# Sheet1.net
KiCad netlist of a schematic drawn in Altium Designer
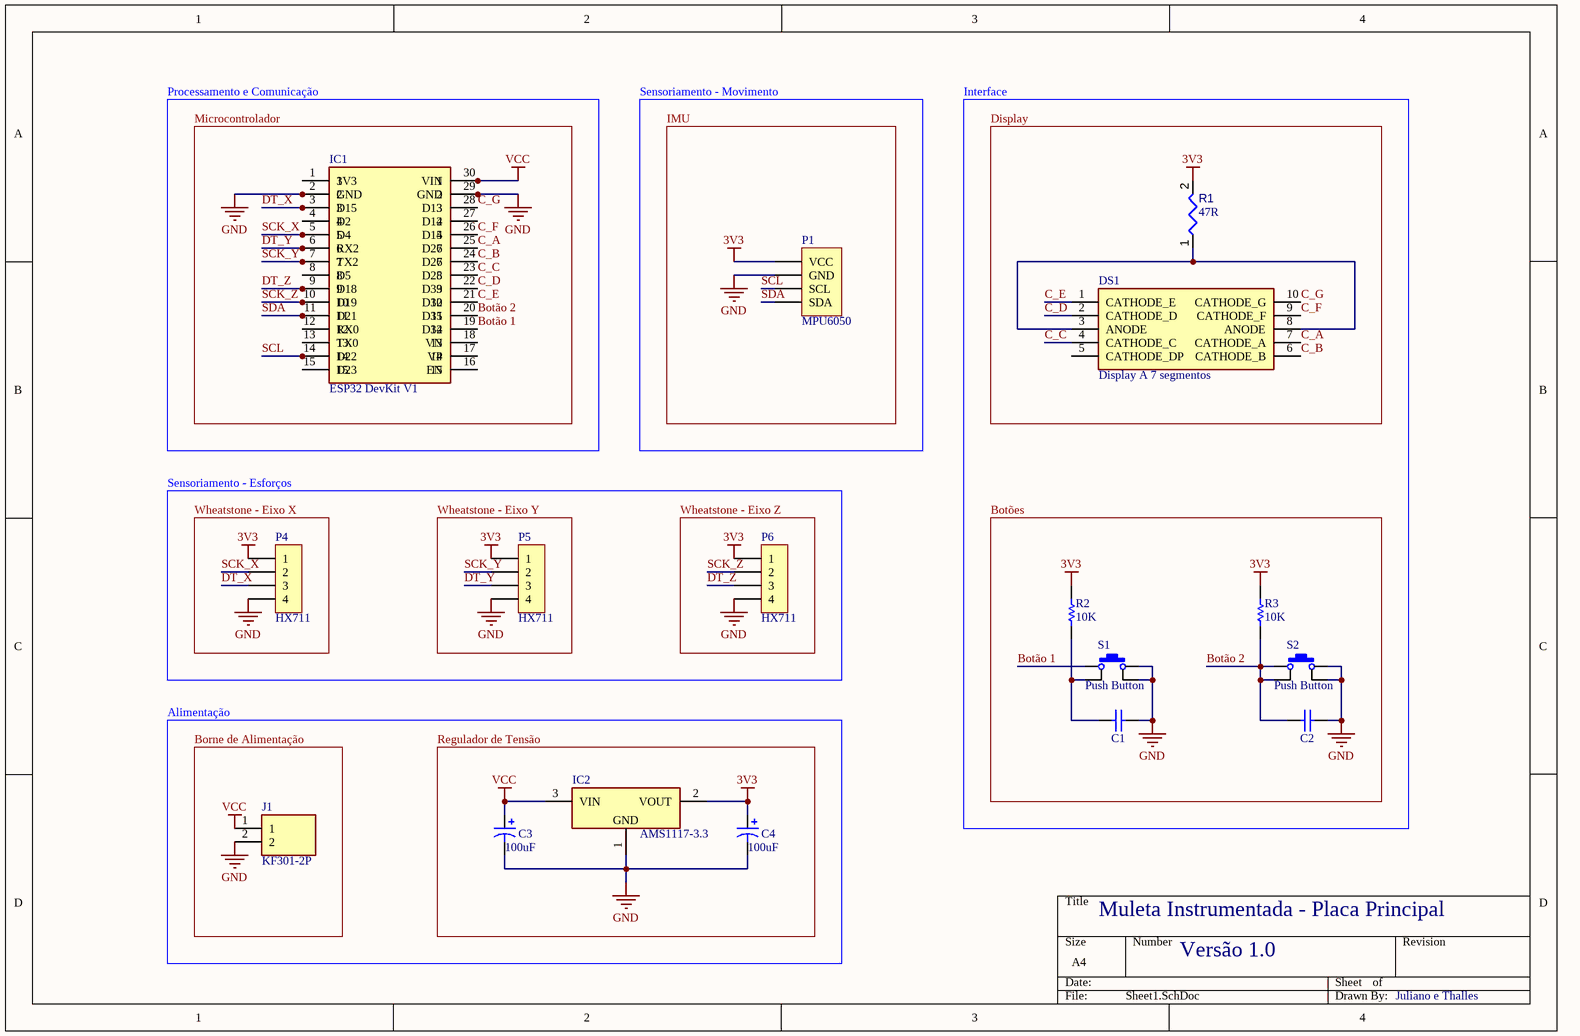
[diagram p0: Sheet1.SchDoc]

(export (version "E")
  (design (tool "Eeschema 10.0.6"))
  (components
    (comp (ref "C1")
      (value "CAP CER DISK 100NF 50V")
      (footprint "CAP CER DISK 100NF 50V")
      (fields (field (name "MANUFACTURER PART NUMBER") "IMP14925"))
      (libsource (lib "ThundeRatz") (part "Symbol"))
    )
    (comp (ref "C2")
      (value "CAP CER DISK 100NF 50V")
      (footprint "CAP CER DISK 100NF 50V")
      (fields (field (name "MANUFACTURER PART NUMBER") "IMP14925"))
      (libsource (lib "ThundeRatz") (part "Symbol"))
    )
    (comp (ref "C3")
      (value "100uF")
      (footprint "CAPPRD250W65D630H900")
      (description "Capacitor Polarised")
      (fields
        (field (name "MANUFACTURER_PART_NUMBER") "16SEPC100MW+S")
        (field (name "MOUSER PART NUMBER") "667-16SEPC100MW+S")
      )
      (libsource (lib "Schlib1") (part "16SEPC100MW+S"))
    )
    (comp (ref "C4")
      (value "100uF")
      (footprint "CAPPRD250W65D630H900")
      (description "Capacitor Polarised")
      (fields
        (field (name "MANUFACTURER_PART_NUMBER") "16SEPC100MW+S")
        (field (name "MOUSER PART NUMBER") "667-16SEPC100MW+S")
      )
      (libsource (lib "Schlib1") (part "16SEPC100MW+S"))
    )
    (comp (ref "DS1")
      (value "Display A 7 segmentos")
      (footprint "PcbLib1:DIPS1524W51P254L1270H825Q10N")
      (description "Display")
      (fields (field (name "MANUFACTURER_PART_NUMBER") "C-551SRD-NW B/W"))
      (libsource (lib "Schlib1") (part "C-551SRD-NW_B_W"))
    )
    (comp (ref "IC1")
      (value "ESP32 DevKit V1")
      (footprint "PcbLib1:ESP32 DevKit V1")
      (libsource (lib "Schlib1") (part "ESP32 DevKit V1"))
    )
    (comp (ref "IC2")
      (value "AMS1117-3.3")
      (footprint "PcbLib1:SOT229P700X180-4N")
      (description "Integrated Circuit")
      (libsource (lib "Schlib1") (part "AMS1117-3.3"))
    )
    (comp (ref "J1")
      (value "KF301-2P")
      (footprint "KF3012P")
      (description "Connector")
      (libsource (lib "Schlib1") (part "KF301-2P"))
    )
    (comp (ref "P1")
      (value "MPU6050")
      (footprint "Pin Header 1x8 TH Pitch 2.54mm")
      (description "Headers & Wire Housings 36Pin 2mm Spacing Single Row Hdrs, 5pc")
      (libsource (lib "Schlib1") (part "MPU6050 module"))
    )
    (comp (ref "P2")
      (value "Header Female 1x15")
      (footprint "HDR FEMALE 1x15")
      (description "Headers & Wire Housings 40Pin 2mm Spacing Single Row Hdrs, 5pc")
      (fields (field (name "MANUFACTURER") "Cromax"))
      (libsource (lib "Schlib1") (part "Header Female 1x15"))
    )
    (comp (ref "P3")
      (value "Header Female 1x15")
      (footprint "HDR FEMALE 1x15")
      (description "Headers & Wire Housings 40Pin 2mm Spacing Single Row Hdrs, 5pc")
      (fields (field (name "MANUFACTURER") "Cromax"))
      (libsource (lib "") (part "Header Female 1x15_1"))
    )
    (comp (ref "P4")
      (value "HX711")
      (footprint "HDR MALE 1x4")
      (description "Headers & Wire Housings 40Pin 2mm Spacing Single Row Hdrs, 5pc")
      (fields (field (name "MANUFACTURER") "Cromax") (field (name "MANUFACTURER PART NUMBER") "IMP10327"))
      (libsource (lib "Schlib1") (part "Header 1x4"))
    )
    (comp (ref "P5")
      (value "HX711")
      (footprint "HDR MALE 1x4")
      (description "Headers & Wire Housings 40Pin 2mm Spacing Single Row Hdrs, 5pc")
      (fields (field (name "MANUFACTURER") "Cromax") (field (name "MANUFACTURER PART NUMBER") "IMP10327"))
      (libsource (lib "Schlib1") (part "Header 1x4"))
    )
    (comp (ref "P6")
      (value "HX711")
      (footprint "HDR MALE 1x4")
      (description "Headers & Wire Housings 40Pin 2mm Spacing Single Row Hdrs, 5pc")
      (fields (field (name "MANUFACTURER") "Cromax") (field (name "MANUFACTURER PART NUMBER") "IMP10327"))
      (libsource (lib "Schlib1") (part "Header 1x4"))
    )
    (comp (ref "R1")
      (value "47R")
      (footprint "RESA60-630X240")
      (description "Axial Resistor, 47.5 Ohm, +/- 1%, 0.25 W, -55 to 155 degC, 2-Pin THD, RoHS, Bulk")
      (fields (field (name "TOLERANCE") "1%") (field (name "MANUFACTURER") "Yageo"))
      (libsource (lib "") (part "RES-2_1"))
    )
    (comp (ref "R2")
      (value "10K")
      (footprint "RESA60-630X240")
      (description "Axial Resistor, 10 KOhm, +/- 1%, 0.25 W, -55 to 155 degC, 2-Pin THD, RoHS, Bulk")
      (fields (field (name "TOLERANCE") "1%") (field (name "MANUFACTURER") "Yageo"))
      (libsource (lib "ThundeRatz") (part "RES-2"))
    )
    (comp (ref "R3")
      (value "10K")
      (footprint "RESA60-630X240")
      (description "Axial Resistor, 10 KOhm, +/- 1%, 0.25 W, -55 to 155 degC, 2-Pin THD, RoHS, Bulk")
      (fields (field (name "TOLERANCE") "1%") (field (name "MANUFACTURER") "Yageo"))
      (libsource (lib "ThundeRatz") (part "RES-2"))
    )
    (comp (ref "S1")
      (value "Push Button")
      (footprint "TACT SWITCH 6X6X7MM")
      (description "SWITCH TACTILE SPST-NO 0.02A 15V")
      (fields
        (field (name "MANUFACTURER") "Panasonic Electronic Components")
        (field (name "MANUFACTURER PART NUMBER") "EVQ-PAC07K")
      )
      (libsource (lib "ThundeRatz") (part "SWITCH TACTILE SPST-NO 0.02A 15V"))
    )
    (comp (ref "S2")
      (value "Push Button")
      (footprint "TACT SWITCH 6X6X7MM")
      (description "SWITCH TACTILE SPST-NO 0.02A 15V")
      (fields
        (field (name "MANUFACTURER") "Panasonic Electronic Components")
        (field (name "MANUFACTURER PART NUMBER") "EVQ-PAC07K")
      )
      (libsource (lib "ThundeRatz") (part "SWITCH TACTILE SPST-NO 0.02A 15V"))
    )
  )
  (nets
    (net (code "1") (name "/Botão 1") (class "Default")
      (node (ref "IC1") (pin "19") (pinfunction "D34_19") (pintype "passive"))
      (node (ref "P3") (pin "12") (pinfunction "12_12") (pintype "power_in"))
      (node (ref "S1") (pin "1") (pinfunction "1_1") (pintype "passive"))
    )
    (net (code "2") (name "/Botão 2") (class "Default")
      (node (ref "C2") (pin "1") (pinfunction "1_1") (pintype "passive"))
      (node (ref "IC1") (pin "20") (pinfunction "D35_20") (pintype "passive"))
      (node (ref "P3") (pin "11") (pinfunction "11_11") (pintype "power_in"))
      (node (ref "R3") (pin "1") (pinfunction "1_1") (pintype "passive"))
      (node (ref "S2") (pin "1") (pinfunction "1_1") (pintype "passive"))
      (node (ref "S2") (pin "2") (pinfunction "2_2") (pintype "passive"))
    )
    (net (code "3") (name "/C_A") (class "Default")
      (node (ref "DS1") (pin "7") (pinfunction "CATHODE_A_7") (pintype "passive"))
      (node (ref "IC1") (pin "25") (pinfunction "D27_25") (pintype "passive"))
      (node (ref "P3") (pin "6") (pinfunction "6_6") (pintype "passive"))
    )
    (net (code "4") (name "/C_B") (class "Default")
      (node (ref "DS1") (pin "6") (pinfunction "CATHODE_B_6") (pintype "passive"))
      (node (ref "IC1") (pin "24") (pinfunction "D26_24") (pintype "passive"))
      (node (ref "P3") (pin "7") (pinfunction "7_7") (pintype "power_in"))
    )
    (net (code "5") (name "/C_C") (class "Default")
      (node (ref "DS1") (pin "4") (pinfunction "CATHODE_C_4") (pintype "passive"))
      (node (ref "IC1") (pin "23") (pinfunction "D25_23") (pintype "passive"))
      (node (ref "P3") (pin "8") (pinfunction "8_8") (pintype "power_in"))
    )
    (net (code "6") (name "/C_D") (class "Default")
      (node (ref "DS1") (pin "2") (pinfunction "CATHODE_D_2") (pintype "passive"))
      (node (ref "IC1") (pin "22") (pinfunction "D33_22") (pintype "passive"))
      (node (ref "P3") (pin "9") (pinfunction "9_9") (pintype "passive"))
    )
    (net (code "7") (name "/C_E") (class "Default")
      (node (ref "DS1") (pin "1") (pinfunction "CATHODE_E_1") (pintype "passive"))
      (node (ref "IC1") (pin "21") (pinfunction "D32_21") (pintype "passive"))
      (node (ref "P3") (pin "10") (pinfunction "10_10") (pintype "passive"))
    )
    (net (code "8") (name "/C_F") (class "Default")
      (node (ref "DS1") (pin "9") (pinfunction "CATHODE_F_9") (pintype "passive"))
      (node (ref "IC1") (pin "26") (pinfunction "D14_26") (pintype "passive"))
      (node (ref "P3") (pin "5") (pinfunction "5_5") (pintype "passive"))
    )
    (net (code "9") (name "/C_G") (class "Default")
      (node (ref "DS1") (pin "10") (pinfunction "CATHODE_G_10") (pintype "passive"))
      (node (ref "IC1") (pin "28") (pinfunction "D13_28") (pintype "passive"))
      (node (ref "P3") (pin "3") (pinfunction "3_3") (pintype "power_in"))
    )
    (net (code "10") (name "/DT_X") (class "Default")
      (node (ref "IC1") (pin "3") (pinfunction "D15_3") (pintype "passive"))
      (node (ref "P2") (pin "3") (pinfunction "3_3") (pintype "power_in"))
      (node (ref "P4") (pin "3") (pinfunction "3_3") (pintype "power_in"))
    )
    (net (code "11") (name "/DT_Y") (class "Default")
      (node (ref "IC1") (pin "6") (pinfunction "RX2_6") (pintype "passive"))
      (node (ref "P2") (pin "6") (pinfunction "6_6") (pintype "passive"))
      (node (ref "P5") (pin "3") (pinfunction "3_3") (pintype "power_in"))
    )
    (net (code "12") (name "/DT_Z") (class "Default")
      (node (ref "IC1") (pin "9") (pinfunction "D18_9") (pintype "passive"))
      (node (ref "P2") (pin "9") (pinfunction "9_9") (pintype "passive"))
      (node (ref "P6") (pin "3") (pinfunction "3_3") (pintype "power_in"))
    )
    (net (code "13") (name "/SCK_X") (class "Default")
      (node (ref "IC1") (pin "5") (pinfunction "D4_5") (pintype "passive"))
      (node (ref "P2") (pin "5") (pinfunction "5_5") (pintype "passive"))
      (node (ref "P4") (pin "2") (pinfunction "2_2") (pintype "passive"))
    )
    (net (code "14") (name "/SCK_Y") (class "Default")
      (node (ref "IC1") (pin "7") (pinfunction "TX2_7") (pintype "passive"))
      (node (ref "P2") (pin "7") (pinfunction "7_7") (pintype "power_in"))
      (node (ref "P5") (pin "2") (pinfunction "2_2") (pintype "passive"))
    )
    (net (code "15") (name "/SCK_Z") (class "Default")
      (node (ref "IC1") (pin "10") (pinfunction "D19_10") (pintype "passive"))
      (node (ref "P2") (pin "10") (pinfunction "10_10") (pintype "passive"))
      (node (ref "P6") (pin "2") (pinfunction "2_2") (pintype "passive"))
    )
    (net (code "16") (name "/SCL") (class "Default")
      (node (ref "IC1") (pin "14") (pinfunction "D22_14") (pintype "passive"))
      (node (ref "P1") (pin "3") (pinfunction "SCL_3") (pintype "passive"))
      (node (ref "P2") (pin "14") (pinfunction "14_14") (pintype "passive"))
    )
    (net (code "17") (name "/SDA") (class "Default")
      (node (ref "IC1") (pin "11") (pinfunction "D21_11") (pintype "passive"))
      (node (ref "P1") (pin "4") (pinfunction "SDA_4") (pintype "passive"))
      (node (ref "P2") (pin "11") (pinfunction "11_11") (pintype "power_in"))
    )
    (net (code "18") (name "3V3") (class "Default")
      (node (ref "C4") (pin "1") (pinfunction "1_1") (pintype "passive"))
      (node (ref "IC2") (pin "2") (pinfunction "VOUT_2") (pintype "passive"))
      (node (ref "P1") (pin "1") (pinfunction "VCC_1") (pintype "passive"))
      (node (ref "P4") (pin "1") (pinfunction "1_1") (pintype "passive"))
      (node (ref "P5") (pin "1") (pinfunction "1_1") (pintype "passive"))
      (node (ref "P6") (pin "1") (pinfunction "1_1") (pintype "passive"))
      (node (ref "R1") (pin "2") (pinfunction "2_2") (pintype "passive"))
      (node (ref "R2") (pin "2") (pinfunction "2_2") (pintype "passive"))
      (node (ref "R3") (pin "2") (pinfunction "2_2") (pintype "passive"))
    )
    (net (code "19") (name "GND") (class "Default")
      (node (ref "C1") (pin "2") (pinfunction "2_2") (pintype "passive"))
      (node (ref "C2") (pin "2") (pinfunction "2_2") (pintype "passive"))
      (node (ref "C3") (pin "2") (pinfunction "2_2") (pintype "passive"))
      (node (ref "C4") (pin "2") (pinfunction "2_2") (pintype "passive"))
      (node (ref "IC1") (pin "2") (pinfunction "GND_2") (pintype "passive"))
      (node (ref "IC1") (pin "29") (pinfunction "GND_29") (pintype "passive"))
      (node (ref "IC2") (pin "1") (pinfunction "GND_1") (pintype "passive"))
      (node (ref "J1") (pin "2") (pinfunction "2_2") (pintype "passive"))
      (node (ref "P1") (pin "2") (pinfunction "GND_2") (pintype "passive"))
      (node (ref "P2") (pin "2") (pinfunction "2_2") (pintype "passive"))
      (node (ref "P3") (pin "2") (pinfunction "2_2") (pintype "passive"))
      (node (ref "P4") (pin "4") (pinfunction "4_4") (pintype "power_in"))
      (node (ref "P5") (pin "4") (pinfunction "4_4") (pintype "power_in"))
      (node (ref "P6") (pin "4") (pinfunction "4_4") (pintype "power_in"))
      (node (ref "S1") (pin "3") (pinfunction "3_3") (pintype "passive"))
      (node (ref "S1") (pin "4") (pinfunction "4_4") (pintype "passive"))
      (node (ref "S2") (pin "3") (pinfunction "3_3") (pintype "passive"))
      (node (ref "S2") (pin "4") (pinfunction "4_4") (pintype "passive"))
    )
    (net (code "20") (name "Net-(C1-Pad1)") (class "Default")
      (node (ref "C1") (pin "1") (pinfunction "1_1") (pintype "passive"))
      (node (ref "R2") (pin "1") (pinfunction "1_1") (pintype "passive"))
      (node (ref "S1") (pin "2") (pinfunction "2_2") (pintype "passive"))
    )
    (net (code "21") (name "Net-(DS1-ANODE-Pad3)") (class "Default")
      (node (ref "DS1") (pin "3") (pinfunction "ANODE_3") (pintype "passive"))
      (node (ref "DS1") (pin "8") (pinfunction "ANODE_8") (pintype "passive"))
      (node (ref "R1") (pin "1") (pinfunction "1_1") (pintype "passive"))
    )
    (net (code "22") (name "Net-(IC1-3V3)") (class "Default")
      (node (ref "IC1") (pin "1") (pinfunction "3V3_1") (pintype "passive"))
      (node (ref "P2") (pin "1") (pinfunction "1_1") (pintype "passive"))
    )
    (net (code "23") (name "Net-(IC1-D2)") (class "Default")
      (node (ref "IC1") (pin "4") (pinfunction "D2_4") (pintype "passive"))
      (node (ref "P2") (pin "4") (pinfunction "4_4") (pintype "power_in"))
    )
    (net (code "24") (name "Net-(IC1-D5)") (class "Default")
      (node (ref "IC1") (pin "8") (pinfunction "D5_8") (pintype "passive"))
      (node (ref "P2") (pin "8") (pinfunction "8_8") (pintype "power_in"))
    )
    (net (code "25") (name "Net-(IC1-D12)") (class "Default")
      (node (ref "IC1") (pin "27") (pinfunction "D12_27") (pintype "passive"))
      (node (ref "P3") (pin "4") (pinfunction "4_4") (pintype "power_in"))
    )
    (net (code "26") (name "Net-(IC1-D23)") (class "Default")
      (node (ref "IC1") (pin "15") (pinfunction "D23_15") (pintype "passive"))
      (node (ref "P2") (pin "15") (pinfunction "15_15") (pintype "power_in"))
    )
    (net (code "27") (name "Net-(IC1-EN)") (class "Default")
      (node (ref "IC1") (pin "16") (pinfunction "EN_16") (pintype "passive"))
      (node (ref "P3") (pin "15") (pinfunction "15_15") (pintype "power_in"))
    )
    (net (code "28") (name "Net-(IC1-RX0)") (class "Default")
      (node (ref "IC1") (pin "12") (pinfunction "RX0_12") (pintype "passive"))
      (node (ref "P2") (pin "12") (pinfunction "12_12") (pintype "power_in"))
    )
    (net (code "29") (name "Net-(IC1-TX0)") (class "Default")
      (node (ref "IC1") (pin "13") (pinfunction "TX0_13") (pintype "passive"))
      (node (ref "P2") (pin "13") (pinfunction "13_13") (pintype "passive"))
    )
    (net (code "30") (name "Net-(IC1-VN)") (class "Default")
      (node (ref "IC1") (pin "18") (pinfunction "VN_18") (pintype "passive"))
      (node (ref "P3") (pin "13") (pinfunction "13_13") (pintype "passive"))
    )
    (net (code "31") (name "Net-(IC1-VP)") (class "Default")
      (node (ref "IC1") (pin "17") (pinfunction "VP_17") (pintype "passive"))
      (node (ref "P3") (pin "14") (pinfunction "14_14") (pintype "passive"))
    )
    (net (code "32") (name "VCC") (class "Default")
      (node (ref "C3") (pin "1") (pinfunction "1_1") (pintype "passive"))
      (node (ref "IC1") (pin "30") (pinfunction "VIN_30") (pintype "passive"))
      (node (ref "IC2") (pin "3") (pinfunction "VIN_3") (pintype "passive"))
      (node (ref "J1") (pin "1") (pinfunction "1_1") (pintype "passive"))
      (node (ref "P3") (pin "1") (pinfunction "1_1") (pintype "passive"))
    )
    (net (code "33") (name "unconnected-(DS1-CATHODE_DP-Pad5)") (class "Default")
      (node (ref "DS1") (pin "5") (pinfunction "CATHODE_DP_5") (pintype "passive"))
    )
  )
)
